# cc1101-sniffer.net
KiCad netlist of a schematic drawn in EAGLE
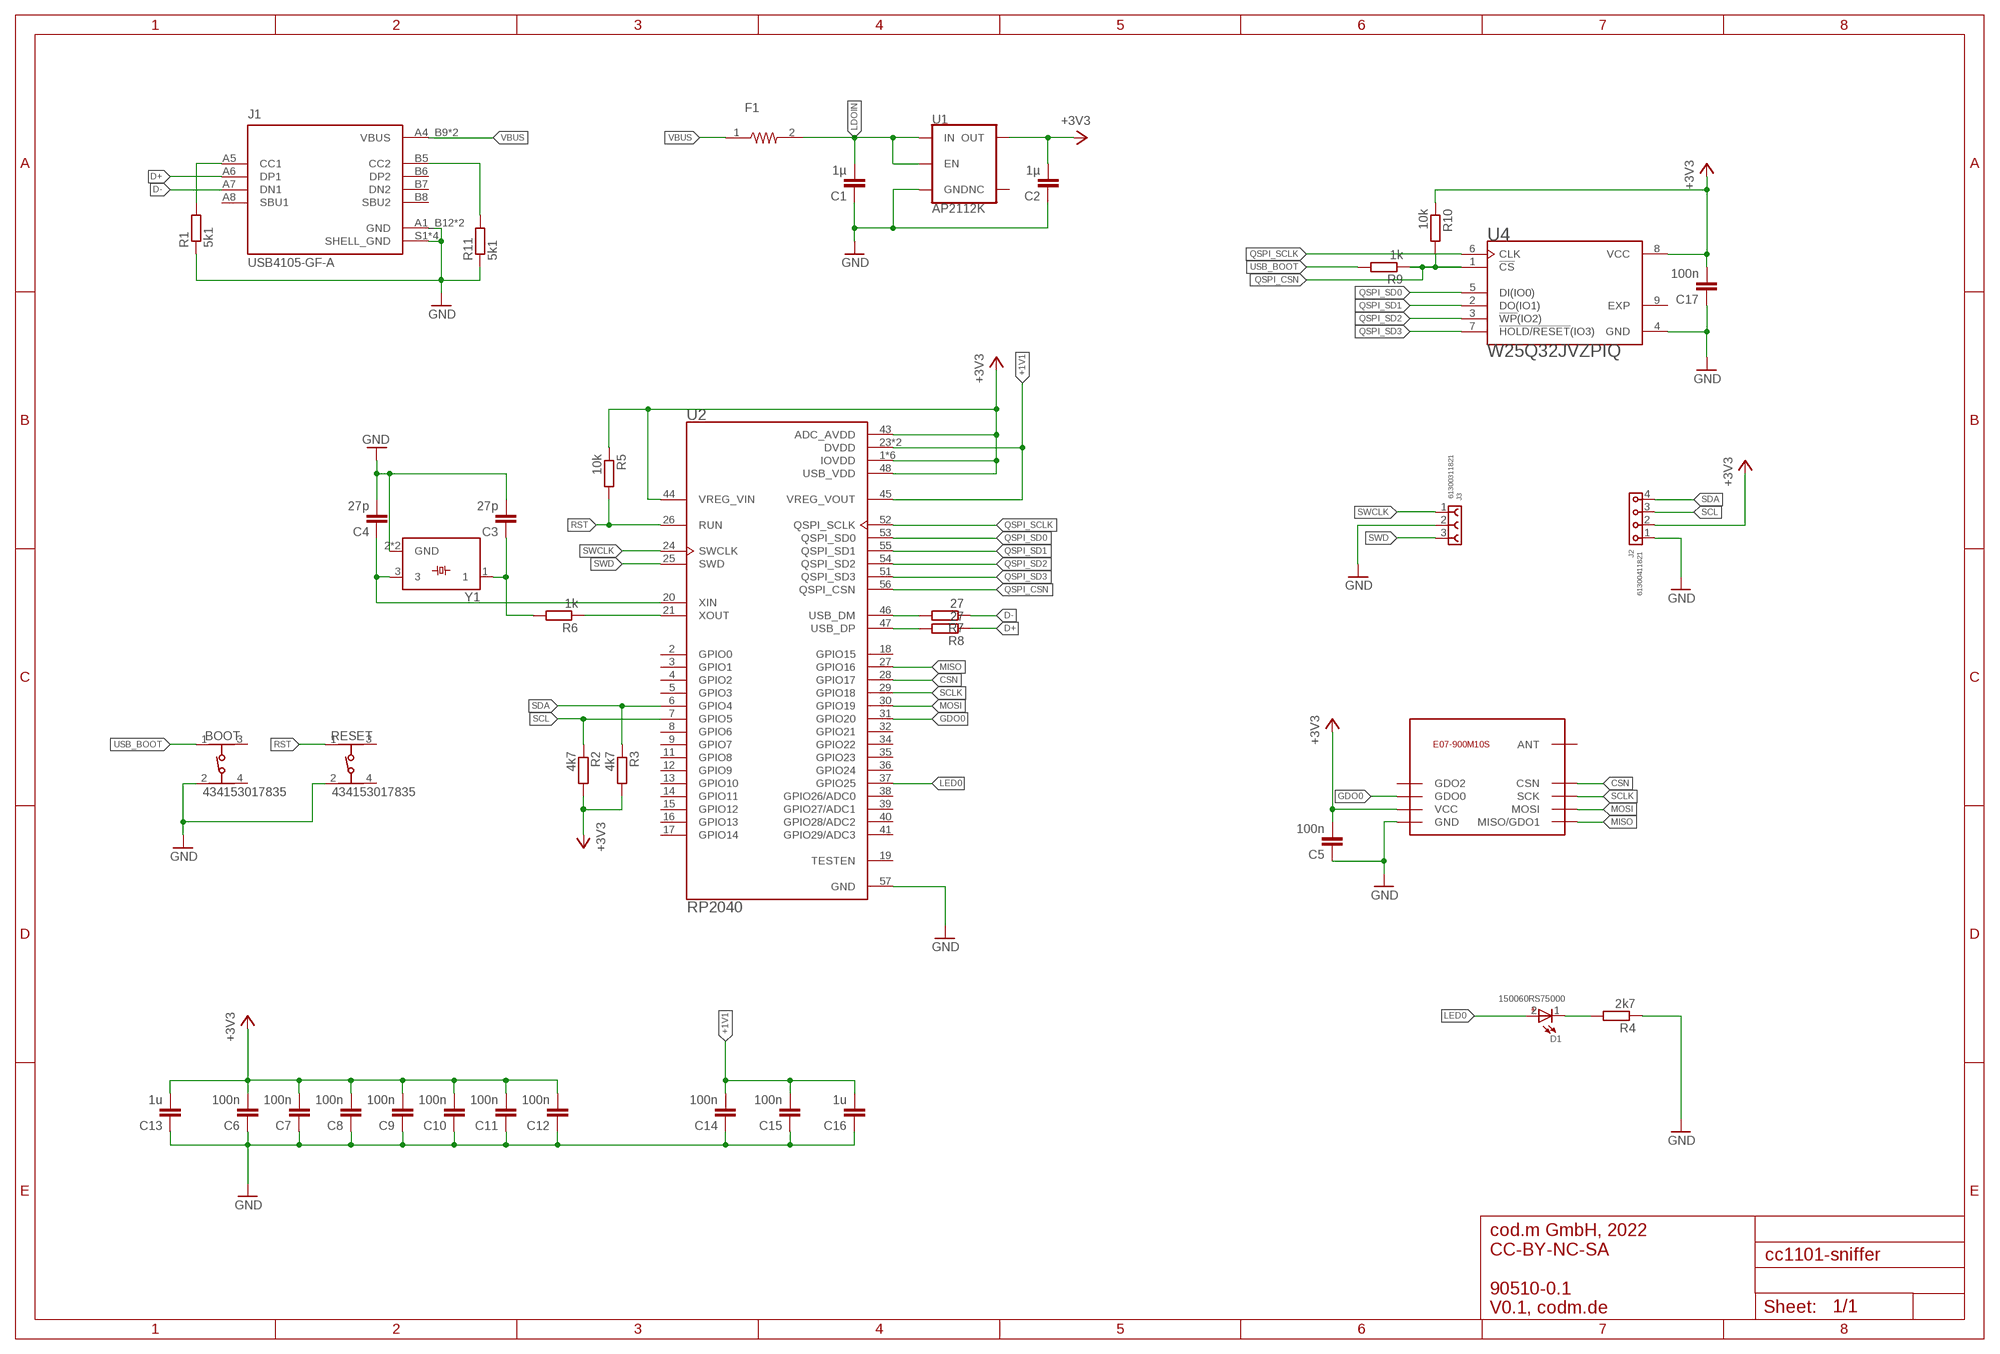
[diagram p0: schematic, sheet 1]

(export (version "E")
  (design (tool "Eeschema 10.0.6"))
  (components
    (comp (ref "BOOT")
      (value "434153017835")
      (footprint "eagle-import:434153017835")
      (libsource (lib "eagle-import") (part "434153017835"))
    )
    (comp (ref "C1")
      (value "1µ")
      (footprint "eagle-import:C0805K")
      (libsource (lib "eagle-import") (part "C-EUC0805K"))
    )
    (comp (ref "C2")
      (value "1µ")
      (footprint "eagle-import:C0805K")
      (libsource (lib "eagle-import") (part "C-EUC0805K"))
    )
    (comp (ref "C3")
      (value "27p")
      (footprint "eagle-import:C0603K")
      (libsource (lib "eagle-import") (part "C-EUC0603K"))
    )
    (comp (ref "C4")
      (value "27p")
      (footprint "eagle-import:C0603K")
      (libsource (lib "eagle-import") (part "C-EUC0603K"))
    )
    (comp (ref "C5")
      (value "100n")
      (footprint "eagle-import:C0603K")
      (libsource (lib "eagle-import") (part "C-EUC0603K"))
    )
    (comp (ref "C6")
      (value "100n")
      (footprint "eagle-import:C0603K")
      (libsource (lib "eagle-import") (part "C-EUC0603K"))
    )
    (comp (ref "C7")
      (value "100n")
      (footprint "eagle-import:C0603K")
      (libsource (lib "eagle-import") (part "C-EUC0603K"))
    )
    (comp (ref "C8")
      (value "100n")
      (footprint "eagle-import:C0603K")
      (libsource (lib "eagle-import") (part "C-EUC0603K"))
    )
    (comp (ref "C9")
      (value "100n")
      (footprint "eagle-import:C0603K")
      (libsource (lib "eagle-import") (part "C-EUC0603K"))
    )
    (comp (ref "C10")
      (value "100n")
      (footprint "eagle-import:C0603K")
      (libsource (lib "eagle-import") (part "C-EUC0603K"))
    )
    (comp (ref "C11")
      (value "100n")
      (footprint "eagle-import:C0603K")
      (libsource (lib "eagle-import") (part "C-EUC0603K"))
    )
    (comp (ref "C12")
      (value "100n")
      (footprint "eagle-import:C0603K")
      (libsource (lib "eagle-import") (part "C-EUC0603K"))
    )
    (comp (ref "C13")
      (value "1u")
      (footprint "eagle-import:C0603K")
      (libsource (lib "eagle-import") (part "C-EUC0603K"))
    )
    (comp (ref "C14")
      (value "100n")
      (footprint "eagle-import:C0603K")
      (libsource (lib "eagle-import") (part "C-EUC0603K"))
    )
    (comp (ref "C15")
      (value "100n")
      (footprint "eagle-import:C0603K")
      (libsource (lib "eagle-import") (part "C-EUC0603K"))
    )
    (comp (ref "C16")
      (value "1u")
      (footprint "eagle-import:C0603K")
      (libsource (lib "eagle-import") (part "C-EUC0603K"))
    )
    (comp (ref "C17")
      (value "100n")
      (footprint "eagle-import:C0603K")
      (libsource (lib "eagle-import") (part "C-EUC0603K"))
    )
    (comp (ref "D1")
      (value "150060RS75000")
      (footprint "eagle-import:WL-SMCW_0603")
      (libsource (lib "eagle-import") (part "WL-SMCW_0603_150060RS75000"))
    )
    (comp (ref "F1")
      (value "PICOSMDC050S-2")
      (footprint "eagle-import:RESC2012X65N")
      (fields (field (name "MF") "Littelfuse Inc."))
      (libsource (lib "eagle-import") (part "PICOSMDC050S-2"))
    )
    (comp (ref "J1")
      (value "USB4105-GF-A")
      (footprint "eagle-import:GCT_USB4105-GF-A")
      (fields (field (name "MF") "GCT"))
      (libsource (lib "eagle-import") (part "USB4105-GF-A"))
    )
    (comp (ref "J2")
      (value "61300411821")
      (footprint "eagle-import:61300411821")
      (libsource (lib "eagle-import") (part "6130XX11821_61300411821"))
    )
    (comp (ref "J3")
      (value "61300311821")
      (footprint "eagle-import:61300311821")
      (libsource (lib "eagle-import") (part "6130XX11821_61300311821"))
    )
    (comp (ref "R1")
      (value "5k1")
      (footprint "eagle-import:R0603RF")
      (libsource (lib "eagle-import") (part "R-EU_R0603RF"))
    )
    (comp (ref "R2")
      (value "4k7")
      (footprint "eagle-import:R0603RF")
      (libsource (lib "eagle-import") (part "R-EU_R0603RF"))
    )
    (comp (ref "R3")
      (value "4k7")
      (footprint "eagle-import:R0603RF")
      (libsource (lib "eagle-import") (part "R-EU_R0603RF"))
    )
    (comp (ref "R4")
      (value "2k7")
      (footprint "eagle-import:R0603RF")
      (libsource (lib "eagle-import") (part "R-EU_R0603RF"))
    )
    (comp (ref "R5")
      (value "10k")
      (footprint "eagle-import:R0603RF")
      (libsource (lib "eagle-import") (part "R-EU_R0603RF"))
    )
    (comp (ref "R6")
      (value "1k")
      (footprint "eagle-import:R0603RF")
      (libsource (lib "eagle-import") (part "R-EU_R0603RF"))
    )
    (comp (ref "R7")
      (value "27")
      (footprint "eagle-import:R0603RF")
      (libsource (lib "eagle-import") (part "R-EU_R0603RF"))
    )
    (comp (ref "R8")
      (value "27")
      (footprint "eagle-import:R0603RF")
      (libsource (lib "eagle-import") (part "R-EU_R0603RF"))
    )
    (comp (ref "R9")
      (value "1k")
      (footprint "eagle-import:R0603RF")
      (libsource (lib "eagle-import") (part "R-EU_R0603RF"))
    )
    (comp (ref "R10")
      (value "10k")
      (footprint "eagle-import:R0603RF")
      (libsource (lib "eagle-import") (part "R-EU_R0603RF"))
    )
    (comp (ref "R11")
      (value "5k1")
      (footprint "eagle-import:R0603RF")
      (libsource (lib "eagle-import") (part "R-EU_R0603RF"))
    )
    (comp (ref "RESET")
      (value "434153017835")
      (footprint "eagle-import:434153017835")
      (libsource (lib "eagle-import") (part "434153017835"))
    )
    (comp (ref "U$6")
      (value "E07-900M10S")
      (footprint "eagle-import:E07-900M10S")
      (libsource (lib "eagle-import") (part "E07-900M10S"))
    )
    (comp (ref "U1")
      (value "AP2112K")
      (footprint "eagle-import:SOT23-5")
      (libsource (lib "eagle-import") (part "V_REG_AP2112K-3.3V"))
    )
    (comp (ref "U2")
      (value "RP2040")
      (footprint "eagle-import:QFN40P700X700X90-57N")
      (fields (field (name "MF") "Raspberry Pi"))
      (libsource (lib "eagle-import") (part "RP2040"))
    )
    (comp (ref "U4")
      (value "W25Q32JVZPIQ")
      (footprint "eagle-import:SON127P600X500X80-9N")
      (fields (field (name "MF") "Winbond"))
      (libsource (lib "eagle-import") (part "W25Q32JVZPIQ"))
    )
    (comp (ref "Y1")
      (value "ABM8G-12.000MHZ-18-D2Y-T3")
      (footprint "eagle-import:OSCSC320X250X100N")
      (fields (field (name "MF") "Abracon"))
      (libsource (lib "eagle-import") (part "ABM8G-12.000MHZ-18-D2Y-T3"))
    )
  )
  (nets
    (net (code "1") (name "+1V1") (class "Default")
      (node (ref "C14") (pin "2") (pinfunction "2_2") (pintype "passive"))
      (node (ref "C15") (pin "2") (pinfunction "2_2") (pintype "passive"))
      (node (ref "C16") (pin "2") (pinfunction "2_2") (pintype "passive"))
      (node (ref "U2") (pin "23") (pinfunction "DVDD_23") (pintype "power_in"))
      (node (ref "U2") (pin "45") (pinfunction "VREG_VOUT_45") (pintype "output"))
      (node (ref "U2") (pin "50") (pinfunction "DVDD_50") (pintype "power_in"))
    )
    (net (code "2") (name "+3V3") (class "Default")
      (node (ref "C10") (pin "2") (pinfunction "2_2") (pintype "passive"))
      (node (ref "C11") (pin "2") (pinfunction "2_2") (pintype "passive"))
      (node (ref "C12") (pin "2") (pinfunction "2_2") (pintype "passive"))
      (node (ref "C13") (pin "2") (pinfunction "2_2") (pintype "passive"))
      (node (ref "C17") (pin "2") (pinfunction "2_2") (pintype "passive"))
      (node (ref "C2") (pin "2") (pinfunction "2_2") (pintype "passive"))
      (node (ref "C5") (pin "2") (pinfunction "2_2") (pintype "passive"))
      (node (ref "C6") (pin "2") (pinfunction "2_2") (pintype "passive"))
      (node (ref "C7") (pin "2") (pinfunction "2_2") (pintype "passive"))
      (node (ref "C8") (pin "2") (pinfunction "2_2") (pintype "passive"))
      (node (ref "C9") (pin "2") (pinfunction "2_2") (pintype "passive"))
      (node (ref "J2") (pin "2") (pinfunction "2_2") (pintype "passive"))
      (node (ref "R10") (pin "1") (pinfunction "1_1") (pintype "passive"))
      (node (ref "R2") (pin "2") (pinfunction "2_2") (pintype "passive"))
      (node (ref "R3") (pin "2") (pinfunction "2_2") (pintype "passive"))
      (node (ref "R5") (pin "1") (pinfunction "1_1") (pintype "passive"))
      (node (ref "U$6") (pin "9") (pinfunction "VCC_9") (pintype "bidirectional"))
      (node (ref "U1") (pin "5") (pinfunction "OUT_5") (pintype "passive"))
      (node (ref "U2") (pin "1") (pinfunction "IOVDD_1") (pintype "power_in"))
      (node (ref "U2") (pin "10") (pinfunction "IOVDD_10") (pintype "power_in"))
      (node (ref "U2") (pin "22") (pinfunction "IOVDD_22") (pintype "power_in"))
      (node (ref "U2") (pin "33") (pinfunction "IOVDD_33") (pintype "power_in"))
      (node (ref "U2") (pin "42") (pinfunction "IOVDD_42") (pintype "power_in"))
      (node (ref "U2") (pin "43") (pinfunction "ADC_AVDD_43") (pintype "power_in"))
      (node (ref "U2") (pin "44") (pinfunction "VREG_VIN_44") (pintype "input"))
      (node (ref "U2") (pin "48") (pinfunction "USB_VDD_48") (pintype "power_in"))
      (node (ref "U2") (pin "49") (pinfunction "IOVDD_49") (pintype "power_in"))
      (node (ref "U4") (pin "8") (pinfunction "VCC_8") (pintype "power_in"))
    )
    (net (code "3") (name "CSN") (class "Default")
      (node (ref "U$6") (pin "19") (pinfunction "CSN_19") (pintype "bidirectional"))
      (node (ref "U2") (pin "28") (pinfunction "GPIO17_28") (pintype "bidirectional"))
    )
    (net (code "4") (name "D+") (class "Default")
      (node (ref "J1") (pin "A6") (pinfunction "DP1_A6") (pintype "bidirectional"))
      (node (ref "R8") (pin "1") (pinfunction "1_1") (pintype "passive"))
    )
    (net (code "5") (name "D-") (class "Default")
      (node (ref "J1") (pin "A7") (pinfunction "DN1_A7") (pintype "bidirectional"))
      (node (ref "R7") (pin "1") (pinfunction "1_1") (pintype "passive"))
    )
    (net (code "6") (name "GDO0") (class "Default")
      (node (ref "U$6") (pin "15") (pinfunction "GDO0_15") (pintype "bidirectional"))
      (node (ref "U2") (pin "31") (pinfunction "GPIO20_31") (pintype "bidirectional"))
    )
    (net (code "7") (name "GND") (class "Default")
      (node (ref "BOOT") (pin "2") (pinfunction "3_2") (pintype "passive"))
      (node (ref "C1") (pin "1") (pinfunction "1_1") (pintype "passive"))
      (node (ref "C10") (pin "1") (pinfunction "1_1") (pintype "passive"))
      (node (ref "C11") (pin "1") (pinfunction "1_1") (pintype "passive"))
      (node (ref "C12") (pin "1") (pinfunction "1_1") (pintype "passive"))
      (node (ref "C13") (pin "1") (pinfunction "1_1") (pintype "passive"))
      (node (ref "C14") (pin "1") (pinfunction "1_1") (pintype "passive"))
      (node (ref "C15") (pin "1") (pinfunction "1_1") (pintype "passive"))
      (node (ref "C16") (pin "1") (pinfunction "1_1") (pintype "passive"))
      (node (ref "C17") (pin "1") (pinfunction "1_1") (pintype "passive"))
      (node (ref "C2") (pin "1") (pinfunction "1_1") (pintype "passive"))
      (node (ref "C3") (pin "2") (pinfunction "2_2") (pintype "passive"))
      (node (ref "C4") (pin "2") (pinfunction "2_2") (pintype "passive"))
      (node (ref "C5") (pin "1") (pinfunction "1_1") (pintype "passive"))
      (node (ref "C6") (pin "1") (pinfunction "1_1") (pintype "passive"))
      (node (ref "C7") (pin "1") (pinfunction "1_1") (pintype "passive"))
      (node (ref "C8") (pin "1") (pinfunction "1_1") (pintype "passive"))
      (node (ref "C9") (pin "1") (pinfunction "1_1") (pintype "passive"))
      (node (ref "J1") (pin "A1_B12") (pinfunction "GND_A1_B12") (pintype "power_in"))
      (node (ref "J1") (pin "B1_A12") (pinfunction "GND_B1_A12") (pintype "power_in"))
      (node (ref "J1") (pin "S1") (pinfunction "SHELL_GND_S1") (pintype "power_in"))
      (node (ref "J1") (pin "S2") (pinfunction "SHELL_GND_S2") (pintype "power_in"))
      (node (ref "J1") (pin "S3") (pinfunction "SHELL_GND_S3") (pintype "power_in"))
      (node (ref "J1") (pin "S4") (pinfunction "SHELL_GND_S4") (pintype "power_in"))
      (node (ref "J2") (pin "1") (pinfunction "1_1") (pintype "passive"))
      (node (ref "J3") (pin "2") (pinfunction "2_2") (pintype "passive"))
      (node (ref "R1") (pin "1") (pinfunction "1_1") (pintype "passive"))
      (node (ref "R11") (pin "1") (pinfunction "1_1") (pintype "passive"))
      (node (ref "R4") (pin "1") (pinfunction "1_1") (pintype "passive"))
      (node (ref "RESET") (pin "2") (pinfunction "3_2") (pintype "passive"))
      (node (ref "U$6") (pin "1") (pinfunction "GND_1") (pintype "bidirectional"))
      (node (ref "U$6") (pin "11") (pinfunction "GND_11") (pintype "bidirectional"))
      (node (ref "U$6") (pin "12") (pinfunction "GND_12") (pintype "bidirectional"))
      (node (ref "U$6") (pin "2") (pinfunction "GND_2") (pintype "bidirectional"))
      (node (ref "U$6") (pin "20") (pinfunction "GND_20") (pintype "bidirectional"))
      (node (ref "U$6") (pin "22") (pinfunction "GND_22") (pintype "bidirectional"))
      (node (ref "U$6") (pin "3") (pinfunction "GND_3") (pintype "bidirectional"))
      (node (ref "U$6") (pin "4") (pinfunction "GND_4") (pintype "bidirectional"))
      (node (ref "U$6") (pin "5") (pinfunction "GND_5") (pintype "bidirectional"))
      (node (ref "U1") (pin "2") (pinfunction "GND_2") (pintype "input"))
      (node (ref "U2") (pin "57") (pinfunction "GND_57") (pintype "power_in"))
      (node (ref "U4") (pin "4") (pinfunction "GND_4") (pintype "power_in"))
      (node (ref "Y1") (pin "2") (pinfunction "GND_2") (pintype "power_in"))
      (node (ref "Y1") (pin "4") (pinfunction "GND_4") (pintype "power_in"))
    )
    (net (code "8") (name "LDOIN") (class "Default")
      (node (ref "C1") (pin "2") (pinfunction "2_2") (pintype "passive"))
      (node (ref "F1") (pin "2") (pinfunction "2_2") (pintype "passive"))
      (node (ref "U1") (pin "1") (pinfunction "IN_1") (pintype "input"))
      (node (ref "U1") (pin "3") (pinfunction "EN_3") (pintype "input"))
    )
    (net (code "9") (name "LED0") (class "Default")
      (node (ref "D1") (pin "2") (pinfunction "+_2") (pintype "passive"))
      (node (ref "U2") (pin "37") (pinfunction "GPIO25_37") (pintype "bidirectional"))
    )
    (net (code "10") (name "MISO") (class "Default")
      (node (ref "U$6") (pin "16") (pinfunction "MISO/GDO1_16") (pintype "bidirectional"))
      (node (ref "U2") (pin "27") (pinfunction "GPIO16_27") (pintype "bidirectional"))
    )
    (net (code "11") (name "MOSI") (class "Default")
      (node (ref "U$6") (pin "17") (pinfunction "MOSI_17") (pintype "bidirectional"))
      (node (ref "U2") (pin "30") (pinfunction "GPIO19_30") (pintype "bidirectional"))
    )
    (net (code "12") (name "Net-(C3-Pad1)") (class "Default")
      (node (ref "C3") (pin "1") (pinfunction "1_1") (pintype "passive"))
      (node (ref "R6") (pin "2") (pinfunction "2_2") (pintype "passive"))
      (node (ref "Y1") (pin "1") (pinfunction "1_1") (pintype "passive"))
    )
    (net (code "13") (name "Net-(D1--)") (class "Default")
      (node (ref "D1") (pin "1") (pinfunction "-_1") (pintype "passive"))
      (node (ref "R4") (pin "2") (pinfunction "2_2") (pintype "passive"))
    )
    (net (code "14") (name "Net-(J1-CC1)") (class "Default")
      (node (ref "J1") (pin "A5") (pinfunction "CC1_A5") (pintype "bidirectional"))
      (node (ref "R1") (pin "2") (pinfunction "2_2") (pintype "passive"))
    )
    (net (code "15") (name "Net-(J1-CC2)") (class "Default")
      (node (ref "J1") (pin "B5") (pinfunction "CC2_B5") (pintype "bidirectional"))
      (node (ref "R11") (pin "2") (pinfunction "2_2") (pintype "passive"))
    )
    (net (code "16") (name "Net-(U2-USB_DM)") (class "Default")
      (node (ref "R7") (pin "2") (pinfunction "2_2") (pintype "passive"))
      (node (ref "U2") (pin "46") (pinfunction "USB_DM_46") (pintype "bidirectional"))
    )
    (net (code "17") (name "Net-(U2-USB_DP)") (class "Default")
      (node (ref "R8") (pin "2") (pinfunction "2_2") (pintype "passive"))
      (node (ref "U2") (pin "47") (pinfunction "USB_DP_47") (pintype "bidirectional"))
    )
    (net (code "18") (name "Net-(U2-XIN)") (class "Default")
      (node (ref "C4") (pin "1") (pinfunction "1_1") (pintype "passive"))
      (node (ref "U2") (pin "20") (pinfunction "XIN_20") (pintype "input"))
      (node (ref "Y1") (pin "3") (pinfunction "3_3") (pintype "passive"))
    )
    (net (code "19") (name "Net-(U2-XOUT)") (class "Default")
      (node (ref "R6") (pin "1") (pinfunction "1_1") (pintype "passive"))
      (node (ref "U2") (pin "21") (pinfunction "XOUT_21") (pintype "output"))
    )
    (net (code "20") (name "QSPI_CSN") (class "Default")
      (node (ref "R10") (pin "2") (pinfunction "2_2") (pintype "passive"))
      (node (ref "R9") (pin "1") (pinfunction "1_1") (pintype "passive"))
      (node (ref "U2") (pin "56") (pinfunction "QSPI_CSN_56") (pintype "bidirectional"))
      (node (ref "U4") (pin "1") (pinfunction "~{CS}_1") (pintype "input"))
    )
    (net (code "21") (name "QSPI_SCLK") (class "Default")
      (node (ref "U2") (pin "52") (pinfunction "QSPI_SCLK_52") (pintype "bidirectional"))
      (node (ref "U4") (pin "6") (pinfunction "CLK_6") (pintype "input"))
    )
    (net (code "22") (name "QSPI_SD0") (class "Default")
      (node (ref "U2") (pin "53") (pinfunction "QSPI_SD0_53") (pintype "bidirectional"))
      (node (ref "U4") (pin "5") (pinfunction "DI(IO0)_5") (pintype "bidirectional"))
    )
    (net (code "23") (name "QSPI_SD1") (class "Default")
      (node (ref "U2") (pin "55") (pinfunction "QSPI_SD1_55") (pintype "bidirectional"))
      (node (ref "U4") (pin "2") (pinfunction "DO(IO1)_2") (pintype "bidirectional"))
    )
    (net (code "24") (name "QSPI_SD2") (class "Default")
      (node (ref "U2") (pin "54") (pinfunction "QSPI_SD2_54") (pintype "bidirectional"))
      (node (ref "U4") (pin "3") (pinfunction "~{WP}(IO2)_3") (pintype "bidirectional"))
    )
    (net (code "25") (name "QSPI_SD3") (class "Default")
      (node (ref "U2") (pin "51") (pinfunction "QSPI_SD3_51") (pintype "bidirectional"))
      (node (ref "U4") (pin "7") (pinfunction "~{HOLD/RESET}(IO3)_7") (pintype "bidirectional"))
    )
    (net (code "26") (name "RST") (class "Default")
      (node (ref "R5") (pin "2") (pinfunction "2_2") (pintype "passive"))
      (node (ref "RESET") (pin "1") (pinfunction "1_1") (pintype "passive"))
      (node (ref "U2") (pin "26") (pinfunction "RUN_26") (pintype "input"))
    )
    (net (code "27") (name "SCL") (class "Default")
      (node (ref "J2") (pin "3") (pinfunction "3_3") (pintype "passive"))
      (node (ref "R2") (pin "1") (pinfunction "1_1") (pintype "passive"))
      (node (ref "U2") (pin "7") (pinfunction "GPIO5_7") (pintype "bidirectional"))
    )
    (net (code "28") (name "SCLK") (class "Default")
      (node (ref "U$6") (pin "18") (pinfunction "SCK_18") (pintype "bidirectional"))
      (node (ref "U2") (pin "29") (pinfunction "GPIO18_29") (pintype "bidirectional"))
    )
    (net (code "29") (name "SDA") (class "Default")
      (node (ref "J2") (pin "4") (pinfunction "4_4") (pintype "passive"))
      (node (ref "R3") (pin "1") (pinfunction "1_1") (pintype "passive"))
      (node (ref "U2") (pin "6") (pinfunction "GPIO4_6") (pintype "bidirectional"))
    )
    (net (code "30") (name "SWCLK") (class "Default")
      (node (ref "J3") (pin "1") (pinfunction "1_1") (pintype "passive"))
      (node (ref "U2") (pin "24") (pinfunction "SWCLK_24") (pintype "input"))
    )
    (net (code "31") (name "SWD") (class "Default")
      (node (ref "J3") (pin "3") (pinfunction "3_3") (pintype "passive"))
      (node (ref "U2") (pin "25") (pinfunction "SWD_25") (pintype "bidirectional"))
    )
    (net (code "32") (name "USB_BOOT") (class "Default")
      (node (ref "BOOT") (pin "1") (pinfunction "1_1") (pintype "passive"))
      (node (ref "R9") (pin "2") (pinfunction "2_2") (pintype "passive"))
    )
    (net (code "33") (name "VBUS") (class "Default")
      (node (ref "F1") (pin "1") (pinfunction "1_1") (pintype "passive"))
      (node (ref "J1") (pin "A4_B9") (pinfunction "VBUS_A4_B9") (pintype "power_in"))
      (node (ref "J1") (pin "B4_A9") (pinfunction "VBUS_B4_A9") (pintype "power_in"))
    )
    (net (code "34") (name "unconnected-(BOOT-2-Pad3)") (class "Default")
      (node (ref "BOOT") (pin "3") (pinfunction "2_3") (pintype "passive"))
    )
    (net (code "35") (name "unconnected-(BOOT-Pad4)") (class "Default")
      (node (ref "BOOT") (pin "4") (pinfunction "4_4") (pintype "passive"))
    )
    (net (code "36") (name "unconnected-(J1-DN2-PadB7)") (class "Default")
      (node (ref "J1") (pin "B7") (pinfunction "DN2_B7") (pintype "bidirectional"))
    )
    (net (code "37") (name "unconnected-(J1-DP2-PadB6)") (class "Default")
      (node (ref "J1") (pin "B6") (pinfunction "DP2_B6") (pintype "bidirectional"))
    )
    (net (code "38") (name "unconnected-(J1-SBU1-PadA8)") (class "Default")
      (node (ref "J1") (pin "A8") (pinfunction "SBU1_A8") (pintype "bidirectional"))
    )
    (net (code "39") (name "unconnected-(J1-SBU2-PadB8)") (class "Default")
      (node (ref "J1") (pin "B8") (pinfunction "SBU2_B8") (pintype "bidirectional"))
    )
    (net (code "40") (name "unconnected-(RESET-2-Pad3)") (class "Default")
      (node (ref "RESET") (pin "3") (pinfunction "2_3") (pintype "passive"))
    )
    (net (code "41") (name "unconnected-(RESET-Pad4)") (class "Default")
      (node (ref "RESET") (pin "4") (pinfunction "4_4") (pintype "passive"))
    )
    (net (code "42") (name "unconnected-(U$6-ANT-Pad21)") (class "Default")
      (node (ref "U$6") (pin "21") (pinfunction "ANT_21") (pintype "bidirectional"))
    )
    (net (code "43") (name "unconnected-(U$6-GDO2-Pad14)") (class "Default")
      (node (ref "U$6") (pin "14") (pinfunction "GDO2_14") (pintype "bidirectional"))
    )
    (net (code "44") (name "unconnected-(U1-NC-Pad4)") (class "Default")
      (node (ref "U1") (pin "4") (pinfunction "NC_4") (pintype "no_connect"))
    )
    (net (code "45") (name "unconnected-(U2-GPIO0-Pad2)") (class "Default")
      (node (ref "U2") (pin "2") (pinfunction "GPIO0_2") (pintype "bidirectional"))
    )
    (net (code "46") (name "unconnected-(U2-GPIO1-Pad3)") (class "Default")
      (node (ref "U2") (pin "3") (pinfunction "GPIO1_3") (pintype "bidirectional"))
    )
    (net (code "47") (name "unconnected-(U2-GPIO2-Pad4)") (class "Default")
      (node (ref "U2") (pin "4") (pinfunction "GPIO2_4") (pintype "bidirectional"))
    )
    (net (code "48") (name "unconnected-(U2-GPIO3-Pad5)") (class "Default")
      (node (ref "U2") (pin "5") (pinfunction "GPIO3_5") (pintype "bidirectional"))
    )
    (net (code "49") (name "unconnected-(U2-GPIO6-Pad8)") (class "Default")
      (node (ref "U2") (pin "8") (pinfunction "GPIO6_8") (pintype "bidirectional"))
    )
    (net (code "50") (name "unconnected-(U2-GPIO7-Pad9)") (class "Default")
      (node (ref "U2") (pin "9") (pinfunction "GPIO7_9") (pintype "bidirectional"))
    )
    (net (code "51") (name "unconnected-(U2-GPIO8-Pad11)") (class "Default")
      (node (ref "U2") (pin "11") (pinfunction "GPIO8_11") (pintype "bidirectional"))
    )
    (net (code "52") (name "unconnected-(U2-GPIO9-Pad12)") (class "Default")
      (node (ref "U2") (pin "12") (pinfunction "GPIO9_12") (pintype "bidirectional"))
    )
    (net (code "53") (name "unconnected-(U2-GPIO10-Pad13)") (class "Default")
      (node (ref "U2") (pin "13") (pinfunction "GPIO10_13") (pintype "bidirectional"))
    )
    (net (code "54") (name "unconnected-(U2-GPIO11-Pad14)") (class "Default")
      (node (ref "U2") (pin "14") (pinfunction "GPIO11_14") (pintype "bidirectional"))
    )
    (net (code "55") (name "unconnected-(U2-GPIO12-Pad15)") (class "Default")
      (node (ref "U2") (pin "15") (pinfunction "GPIO12_15") (pintype "bidirectional"))
    )
    (net (code "56") (name "unconnected-(U2-GPIO13-Pad16)") (class "Default")
      (node (ref "U2") (pin "16") (pinfunction "GPIO13_16") (pintype "bidirectional"))
    )
    (net (code "57") (name "unconnected-(U2-GPIO14-Pad17)") (class "Default")
      (node (ref "U2") (pin "17") (pinfunction "GPIO14_17") (pintype "bidirectional"))
    )
    (net (code "58") (name "unconnected-(U2-GPIO15-Pad18)") (class "Default")
      (node (ref "U2") (pin "18") (pinfunction "GPIO15_18") (pintype "bidirectional"))
    )
    (net (code "59") (name "unconnected-(U2-GPIO21-Pad32)") (class "Default")
      (node (ref "U2") (pin "32") (pinfunction "GPIO21_32") (pintype "bidirectional"))
    )
    (net (code "60") (name "unconnected-(U2-GPIO22-Pad34)") (class "Default")
      (node (ref "U2") (pin "34") (pinfunction "GPIO22_34") (pintype "bidirectional"))
    )
    (net (code "61") (name "unconnected-(U2-GPIO23-Pad35)") (class "Default")
      (node (ref "U2") (pin "35") (pinfunction "GPIO23_35") (pintype "bidirectional"))
    )
    (net (code "62") (name "unconnected-(U2-GPIO24-Pad36)") (class "Default")
      (node (ref "U2") (pin "36") (pinfunction "GPIO24_36") (pintype "bidirectional"))
    )
    (net (code "63") (name "unconnected-(U2-GPIO26{slash}ADC0-Pad38)") (class "Default")
      (node (ref "U2") (pin "38") (pinfunction "GPIO26/ADC0_38") (pintype "bidirectional"))
    )
    (net (code "64") (name "unconnected-(U2-GPIO27{slash}ADC1-Pad39)") (class "Default")
      (node (ref "U2") (pin "39") (pinfunction "GPIO27/ADC1_39") (pintype "bidirectional"))
    )
    (net (code "65") (name "unconnected-(U2-GPIO28{slash}ADC2-Pad40)") (class "Default")
      (node (ref "U2") (pin "40") (pinfunction "GPIO28/ADC2_40") (pintype "bidirectional"))
    )
    (net (code "66") (name "unconnected-(U2-GPIO29{slash}ADC3-Pad41)") (class "Default")
      (node (ref "U2") (pin "41") (pinfunction "GPIO29/ADC3_41") (pintype "bidirectional"))
    )
    (net (code "67") (name "unconnected-(U2-TESTEN-Pad19)") (class "Default")
      (node (ref "U2") (pin "19") (pinfunction "TESTEN_19") (pintype "passive"))
    )
    (net (code "68") (name "unconnected-(U4-EXP-Pad9)") (class "Default")
      (node (ref "U4") (pin "9") (pinfunction "EXP_9") (pintype "passive"))
    )
  )
)
